# Szymon_Sochaj_schemat1.net
KiCad netlist of a schematic drawn in EAGLE
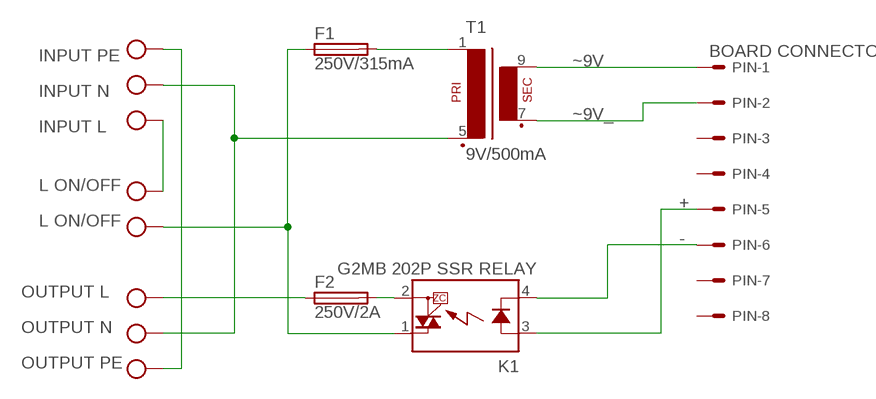
[diagram p0: schematic, sheet 1]

(export (version "E")
  (design (tool "Eeschema 10.0.6"))
  (components
    (comp (ref "F1")
      (value "250V/315mA")
      (footprint "eagle-import:SMIWPROJEKT_FUSE_HOLDER_5X20MM")
      (libsource (lib "eagle-import") (part "SMIWPROJEKT_FUSEBLANK_5X20MM"))
    )
    (comp (ref "F2")
      (value "250V/2A")
      (footprint "eagle-import:SMIWPROJEKT_FUSE_HOLDER_5X20MM")
      (libsource (lib "eagle-import") (part "SMIWPROJEKT_FUSEBLANK_5X20MM"))
    )
    (comp (ref "K1")
      (value "G2MB 202P SSR RELAY")
      (footprint "eagle-import:SMIWPROJEKT_OMRON-G3MB-202P-SSR")
      (libsource (lib "eagle-import") (part "SMIWPROJEKT_OMRON-G3MB-202P-SSR"))
    )
    (comp (ref "PIN")
      (value "BOARD CONNECTOR")
      (footprint "eagle-import:CON-MOLEX_7395-08")
      (fields (field (name "MF") "MOLEX"))
      (libsource (lib "eagle-import") (part "CON-MOLEX_22-?-0805-7088"))
    )
    (comp (ref "T1")
      (value "9V/500mA")
      (footprint "eagle-import:SMIWPROJEKT_VR11")
      (libsource (lib "eagle-import") (part "SMIWPROJEKT_VR11"))
    )
    (comp (ref "X1")
      (value "CON-PTR500_AK300/3")
      (footprint "eagle-import:CON-PTR500_AK300_3")
      (fields (field (name "L") "INPUT L") (field (name "N") "INPUT N") (field (name "PE") "INPUT PE"))
      (libsource (lib "eagle-import") (part "CON-PTR500_AK300/3"))
    )
    (comp (ref "X2")
      (value "CON-PTR500_AK300/3")
      (footprint "eagle-import:CON-PTR500_AK300_3")
      (fields (field (name "L") "OUTPUT L") (field (name "N") "OUTPUT N") (field (name "PE") "OUTPUT PE"))
      (libsource (lib "eagle-import") (part "CON-PTR500_AK300/3"))
    )
    (comp (ref "X3")
      (value "CON-PTR500_AK300/2")
      (footprint "eagle-import:CON-PTR500_AK300_2")
      (fields (field (name "L") "L ON/OFF"))
      (libsource (lib "eagle-import") (part "CON-PTR500_AK300/2"))
    )
  )
  (nets
    (net (code "1") (name "/+") (class "Default")
      (node (ref "K1") (pin "3") (pinfunction "A_3") (pintype "passive"))
      (node (ref "PIN") (pin "5") (pinfunction "S_5") (pintype "passive"))
    )
    (net (code "2") (name "/-") (class "Default")
      (node (ref "K1") (pin "4") (pinfunction "K_4") (pintype "passive"))
      (node (ref "PIN") (pin "6") (pinfunction "S_6") (pintype "passive"))
    )
    (net (code "3") (name "/~{9V_}") (class "Default")
      (node (ref "PIN") (pin "2") (pinfunction "S_2") (pintype "passive"))
      (node (ref "T1") (pin "7") (pinfunction "S3_7") (pintype "passive"))
    )
    (net (code "4") (name "/~{9V}") (class "Default")
      (node (ref "PIN") (pin "1") (pinfunction "S_1") (pintype "passive"))
      (node (ref "T1") (pin "9") (pinfunction "S4_9") (pintype "passive"))
    )
    (net (code "5") (name "Net-(K1-DS1)") (class "Default")
      (node (ref "F1") (pin "1") (pinfunction "1_1") (pintype "passive"))
      (node (ref "K1") (pin "1") (pinfunction "DS1_1") (pintype "passive"))
      (node (ref "X3") (pin "2") (pinfunction "KL_2") (pintype "passive"))
    )
    (net (code "6") (name "Net-(K1-DS2)") (class "Default")
      (node (ref "F2") (pin "2") (pinfunction "2_2") (pintype "passive"))
      (node (ref "K1") (pin "2") (pinfunction "DS2_2") (pintype "passive"))
    )
    (net (code "7") (name "Net-(T1-P1)") (class "Default")
      (node (ref "F1") (pin "2") (pinfunction "2_2") (pintype "passive"))
      (node (ref "T1") (pin "1") (pinfunction "P1_1") (pintype "passive"))
    )
    (net (code "8") (name "Net-(T1-P2)") (class "Default")
      (node (ref "T1") (pin "5") (pinfunction "P2_5") (pintype "passive"))
      (node (ref "X1") (pin "2") (pinfunction "KL_2") (pintype "passive"))
      (node (ref "X2") (pin "2") (pinfunction "KL_2") (pintype "passive"))
    )
    (net (code "9") (name "Net-(X1A-KL)") (class "Default")
      (node (ref "X1") (pin "1") (pinfunction "KL_1") (pintype "passive"))
      (node (ref "X3") (pin "1") (pinfunction "KL_1") (pintype "passive"))
    )
    (net (code "10") (name "Net-(X1C-KL)") (class "Default")
      (node (ref "X1") (pin "3") (pinfunction "KL_3") (pintype "passive"))
      (node (ref "X2") (pin "3") (pinfunction "KL_3") (pintype "passive"))
    )
    (net (code "11") (name "Net-(X2A-KL)") (class "Default")
      (node (ref "F2") (pin "1") (pinfunction "1_1") (pintype "passive"))
      (node (ref "X2") (pin "1") (pinfunction "KL_1") (pintype "passive"))
    )
    (net (code "12") (name "unconnected-(PINC-S-Pad3)") (class "Default")
      (node (ref "PIN") (pin "3") (pinfunction "S_3") (pintype "passive"))
    )
    (net (code "13") (name "unconnected-(PIND-S-Pad4)") (class "Default")
      (node (ref "PIN") (pin "4") (pinfunction "S_4") (pintype "passive"))
    )
    (net (code "14") (name "unconnected-(PING-S-Pad7)") (class "Default")
      (node (ref "PIN") (pin "7") (pinfunction "S_7") (pintype "passive"))
    )
    (net (code "15") (name "unconnected-(PINH-S-Pad8)") (class "Default")
      (node (ref "PIN") (pin "8") (pinfunction "S_8") (pintype "passive"))
    )
  )
)
